# ZP.net
KiCad netlist of a schematic drawn in Altium Designer
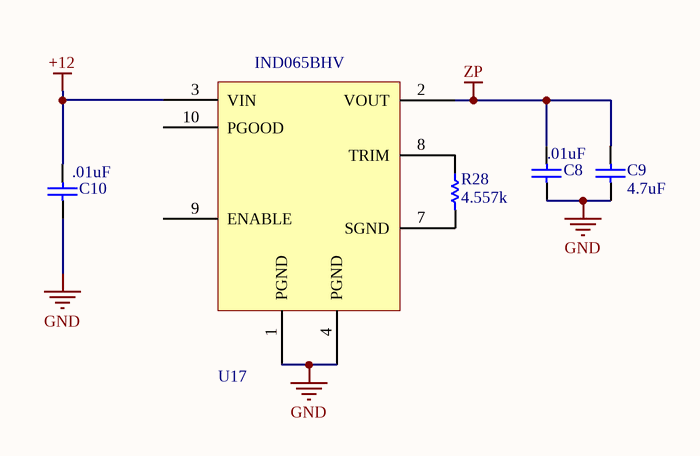
[diagram p0: ZP.SchDoc]

(export (version "E")
  (design (tool "Eeschema 10.0.6"))
  (components
    (comp (ref "C8")
      (value ".01uF")
      (footprint "CAPC0805(2012)145_N")
      (description "CAP CER 0.1UF 25V X7R 0805")
      (libsource (lib "Altium Content Vault") (part "CMP-1036-04795-1"))
    )
    (comp (ref "C9")
      (value "4.7uF")
      (footprint "CAPC1210(3225)170_M")
      (description "CAP 4.7uF 100V ±2% 1210 (3225 Metric) Thickness 1.7mm SMD")
      (fields (field (name "TOLERANCE") "Â±2%"))
      (libsource (lib "Altium Content Vault") (part "CMP-1038-00473-1"))
    )
    (comp (ref "C10")
      (value ".01uF")
      (footprint "CAPC0805(2012)145_N")
      (description "CAP CER 0.1UF 25V X7R 0805")
      (libsource (lib "Altium Content Vault") (part "CMP-1036-04795-1"))
    )
    (comp (ref "R28")
      (value "4.557k")
      (footprint "RESC0805(2012)_L")
      (description "RES SMD 56.2K OHM JUMPER 1/8W 0805")
      (libsource (lib "Altium Content Vault") (part "CMP-1013-00215-1"))
    )
    (comp (ref "U17")
      (value "IND065BHV")
      (footprint "IND065BHV")
      (libsource (lib "ZLS_Schematic_lib") (part "IND065BHV"))
    )
  )
  (nets
    (net (code "1") (name "+12") (class "Default")
      (node (ref "C10") (pin "2") (pinfunction "2_2") (pintype "passive"))
      (node (ref "U17") (pin "3") (pinfunction "VIN_3") (pintype "passive"))
    )
    (net (code "2") (name "GND") (class "Default")
      (node (ref "C10") (pin "1") (pinfunction "1_1") (pintype "passive"))
      (node (ref "C8") (pin "1") (pinfunction "1_1") (pintype "passive"))
      (node (ref "C9") (pin "1") (pinfunction "1_1") (pintype "passive"))
      (node (ref "U17") (pin "1") (pinfunction "PGND_1") (pintype "passive"))
      (node (ref "U17") (pin "4") (pinfunction "PGND_4") (pintype "passive"))
    )
    (net (code "3") (name "Net-(U17-SGND)") (class "Default")
      (node (ref "R28") (pin "2") (pinfunction "2_2") (pintype "passive"))
      (node (ref "U17") (pin "7") (pinfunction "SGND_7") (pintype "passive"))
    )
    (net (code "4") (name "Net-(U17-TRIM)") (class "Default")
      (node (ref "R28") (pin "1") (pinfunction "1_1") (pintype "passive"))
      (node (ref "U17") (pin "8") (pinfunction "TRIM_8") (pintype "passive"))
    )
    (net (code "5") (name "ZP") (class "Default")
      (node (ref "C8") (pin "2") (pinfunction "2_2") (pintype "passive"))
      (node (ref "C9") (pin "2") (pinfunction "2_2") (pintype "passive"))
      (node (ref "U17") (pin "2") (pinfunction "VOUT_2") (pintype "passive"))
    )
    (net (code "6") (name "unconnected-(U17-ENABLE-Pad9)") (class "Default")
      (node (ref "U17") (pin "9") (pinfunction "ENABLE_9") (pintype "passive"))
    )
    (net (code "7") (name "unconnected-(U17-PGOOD-Pad10)") (class "Default")
      (node (ref "U17") (pin "10") (pinfunction "PGOOD_10") (pintype "passive"))
    )
  )
)
